# MySens-GWeasySensRS485-V01-014.net
KiCad netlist of a schematic drawn in EAGLE
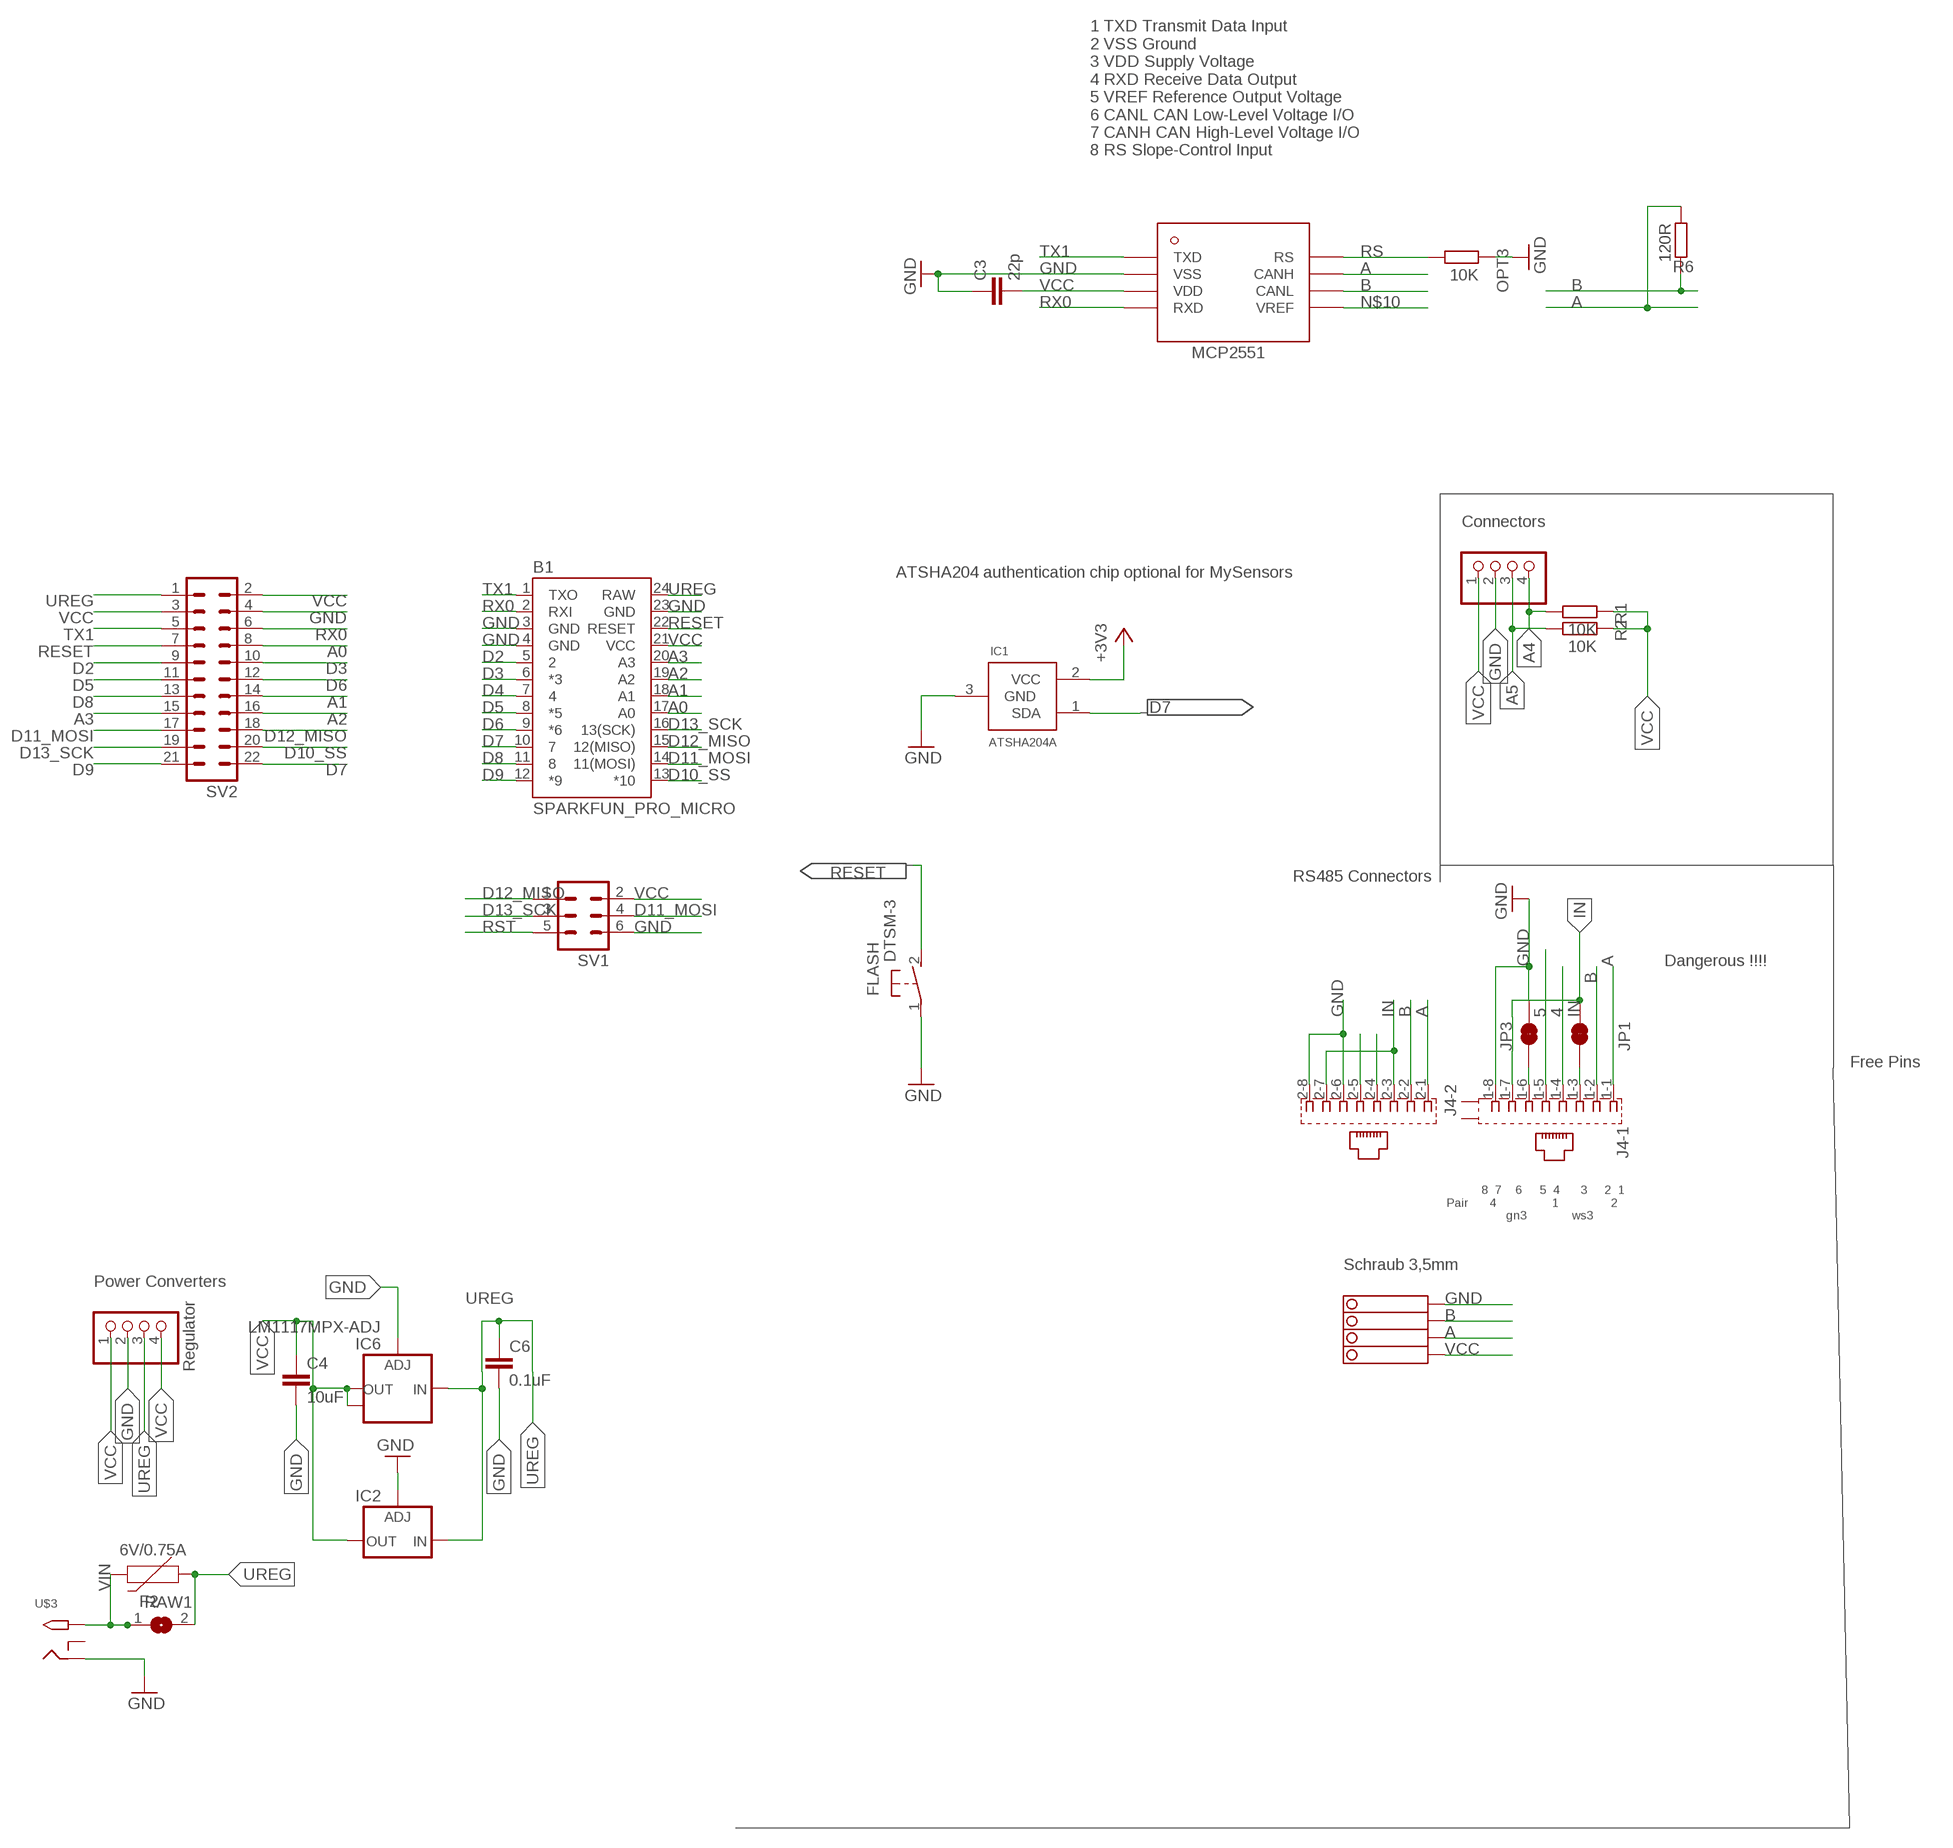
[diagram p0: schematic, sheet 1]

(export (version "E")
  (design (tool "Eeschema 10.0.6"))
  (components
    (comp (ref "B1")
      (value "SPARKFUN_PRO_MICRO")
      (footprint "eagle-import:SPARKFUN_PRO_MICRO")
      (libsource (lib "eagle-import") (part "SPARKFUN_PRO_MICRO"))
    )
    (comp (ref "C3")
      (value "22p")
      (footprint "eagle-import:C0805")
      (libsource (lib "eagle-import") (part "C-EUC0805"))
    )
    (comp (ref "C4")
      (value "10uF")
      (footprint "eagle-import:C1210")
      (libsource (lib "eagle-import") (part "C-EUC1210"))
    )
    (comp (ref "C6")
      (value "0.1uF")
      (footprint "eagle-import:C1206")
      (libsource (lib "eagle-import") (part "C-EUC1206"))
    )
    (comp (ref "F2")
      (value "6V/0.75A")
      (footprint "eagle-import:1206")
      (libsource (lib "eagle-import") (part "PPTC_THREE-QUARTER-AMP"))
    )
    (comp (ref "FLASH")
      (value "DTSM-3")
      (footprint "eagle-import:DTSM-3")
      (libsource (lib "eagle-import") (part "DTSM-3"))
    )
    (comp (ref "IC1")
      (value "ATSHA204A")
      (footprint "eagle-import:SOT23")
      (libsource (lib "eagle-import") (part "ATSHA204A"))
    )
    (comp (ref "IC2")
      (value "LD117ADT50TR")
      (footprint "eagle-import:DPACK")
      (libsource (lib "eagle-import") (part "LD117A?DT50TR"))
    )
    (comp (ref "IC6")
      (value "LM1117MPX-ADJ")
      (footprint "eagle-import:SOT223")
      (libsource (lib "eagle-import") (part "LM1117MPX-ADJ"))
    )
    (comp (ref "J4")
      (value "RJ45_2X_NARROW_SHILDPINS_NOCASE")
      (footprint "eagle-import:RJ45_2X_NARROW_SHILDPINS_NOCASE")
      (libsource (lib "eagle-import") (part "RJ45_2X_NARROW_SHILDPINS_NOCASE"))
    )
    (comp (ref "JP1")
      (value "JUMPER-SMT_2_NC_TRACE_SILK")
      (footprint "eagle-import:SMT-JUMPER_2_NC_TRACE_SILK")
      (libsource (lib "eagle-import") (part "JUMPER-SMT_2_NC_TRACE_SILK"))
    )
    (comp (ref "JP3")
      (value "JUMPER-SMT_2_NC_TRACE_SILK")
      (footprint "eagle-import:SMT-JUMPER_2_NC_TRACE_SILK")
      (libsource (lib "eagle-import") (part "JUMPER-SMT_2_NC_TRACE_SILK"))
    )
    (comp (ref "JP10")
      (value "PINHD-1X04_2.54-S")
      (footprint "eagle-import:1X04-S")
      (libsource (lib "eagle-import") (part "PINHD-1X04_2.54-S"))
    )
    (comp (ref "OPT3")
      (value "10K")
      (footprint "eagle-import:R0805")
      (libsource (lib "eagle-import") (part "R-EU_R0805"))
    )
    (comp (ref "R1")
      (value "10K")
      (footprint "eagle-import:R0805")
      (libsource (lib "eagle-import") (part "R-EU_R0805"))
    )
    (comp (ref "R2")
      (value "10K")
      (footprint "eagle-import:R0805")
      (libsource (lib "eagle-import") (part "R-EU_R0805"))
    )
    (comp (ref "R6")
      (value "120R")
      (footprint "eagle-import:R0805")
      (libsource (lib "eagle-import") (part "R-EU_R0805"))
    )
    (comp (ref "RAW1")
      (value "SJ")
      (footprint "eagle-import:SJ")
      (libsource (lib "eagle-import") (part "SJ"))
    )
    (comp (ref "STEPDWN")
      (value "PINHD-1X04_2.54-S")
      (footprint "eagle-import:1X04-S")
      (libsource (lib "eagle-import") (part "PINHD-1X04_2.54-S"))
    )
    (comp (ref "SV1")
      (value "MA03-2")
      (footprint "eagle-import:MA03-2")
      (libsource (lib "eagle-import") (part "MA03-2"))
    )
    (comp (ref "SV2")
      (value "MA11-2")
      (footprint "eagle-import:MA11-2")
      (libsource (lib "eagle-import") (part "MA11-2"))
    )
    (comp (ref "U$1")
      (value "MCP2551")
      (footprint "eagle-import:SOIC-8")
      (libsource (lib "eagle-import") (part "MCP2551"))
    )
    (comp (ref "U$3")
      (value "2.1MMJACKTHM")
      (footprint "eagle-import:PJ-102A")
      (libsource (lib "eagle-import") (part "2.1MMJACKTHM"))
    )
    (comp (ref "X4")
      (value "1751264")
      (footprint "eagle-import:1751264")
      (libsource (lib "eagle-import") (part "1751264"))
    )
  )
  (nets
    (net (code "1") (name "+3V3") (class "Default")
      (node (ref "IC1") (pin "2") (pinfunction "VCC_2") (pintype "bidirectional"))
    )
    (net (code "2") (name "/4") (class "Default")
      (node (ref "J4") (pin "1-4") (pinfunction "4_1-4") (pintype "passive"))
    )
    (net (code "3") (name "/5") (class "Default")
      (node (ref "J4") (pin "1-5") (pinfunction "5_1-5") (pintype "passive"))
    )
    (net (code "4") (name "/A") (class "Default")
      (node (ref "J4") (pin "1-1") (pinfunction "1_1-1") (pintype "passive"))
      (node (ref "J4") (pin "2-1") (pinfunction "1_2-1") (pintype "passive"))
      (node (ref "R6") (pin "1") (pinfunction "1_1") (pintype "passive"))
      (node (ref "U$1") (pin "CANH") (pinfunction "CANH_CANH") (pintype "bidirectional"))
      (node (ref "X4") (pin "2") (pinfunction "K_2") (pintype "passive"))
    )
    (net (code "5") (name "/A0") (class "Default")
      (node (ref "B1") (pin "17") (pinfunction "A0_17") (pintype "bidirectional"))
      (node (ref "SV2") (pin "8") (pinfunction "8_8") (pintype "passive"))
    )
    (net (code "6") (name "/A1") (class "Default")
      (node (ref "B1") (pin "18") (pinfunction "A1_18") (pintype "bidirectional"))
      (node (ref "SV2") (pin "14") (pinfunction "14_14") (pintype "passive"))
    )
    (net (code "7") (name "/A2") (class "Default")
      (node (ref "B1") (pin "19") (pinfunction "A2_19") (pintype "bidirectional"))
      (node (ref "SV2") (pin "16") (pinfunction "16_16") (pintype "passive"))
    )
    (net (code "8") (name "/A3") (class "Default")
      (node (ref "B1") (pin "20") (pinfunction "A3_20") (pintype "bidirectional"))
      (node (ref "SV2") (pin "15") (pinfunction "15_15") (pintype "passive"))
    )
    (net (code "9") (name "/B") (class "Default")
      (node (ref "J4") (pin "1-2") (pinfunction "2_1-2") (pintype "passive"))
      (node (ref "J4") (pin "2-2") (pinfunction "2_2-2") (pintype "passive"))
      (node (ref "R6") (pin "2") (pinfunction "2_2") (pintype "passive"))
      (node (ref "U$1") (pin "CANL") (pinfunction "CANL_CANL") (pintype "bidirectional"))
      (node (ref "X4") (pin "3") (pinfunction "K_3") (pintype "passive"))
    )
    (net (code "10") (name "/D2") (class "Default")
      (node (ref "B1") (pin "5") (pinfunction "2_5") (pintype "bidirectional"))
      (node (ref "SV2") (pin "9") (pinfunction "9_9") (pintype "passive"))
    )
    (net (code "11") (name "/D3") (class "Default")
      (node (ref "B1") (pin "6") (pinfunction "*3_6") (pintype "bidirectional"))
      (node (ref "SV2") (pin "10") (pinfunction "10_10") (pintype "passive"))
    )
    (net (code "12") (name "/D4") (class "Default")
      (node (ref "B1") (pin "7") (pinfunction "4_7") (pintype "bidirectional"))
    )
    (net (code "13") (name "/D5") (class "Default")
      (node (ref "B1") (pin "8") (pinfunction "*5_8") (pintype "bidirectional"))
      (node (ref "SV2") (pin "11") (pinfunction "11_11") (pintype "passive"))
    )
    (net (code "14") (name "/D6") (class "Default")
      (node (ref "B1") (pin "9") (pinfunction "*6_9") (pintype "bidirectional"))
      (node (ref "SV2") (pin "12") (pinfunction "12_12") (pintype "passive"))
    )
    (net (code "15") (name "/D7") (class "Default")
      (node (ref "B1") (pin "10") (pinfunction "7_10") (pintype "bidirectional"))
      (node (ref "IC1") (pin "1") (pinfunction "SDA_1") (pintype "bidirectional"))
      (node (ref "SV2") (pin "22") (pinfunction "22_22") (pintype "passive"))
    )
    (net (code "16") (name "/D8") (class "Default")
      (node (ref "B1") (pin "11") (pinfunction "8_11") (pintype "bidirectional"))
      (node (ref "SV2") (pin "13") (pinfunction "13_13") (pintype "passive"))
    )
    (net (code "17") (name "/D9") (class "Default")
      (node (ref "B1") (pin "12") (pinfunction "*9_12") (pintype "bidirectional"))
      (node (ref "SV2") (pin "21") (pinfunction "21_21") (pintype "passive"))
    )
    (net (code "18") (name "/D10_SS") (class "Default")
      (node (ref "B1") (pin "13") (pinfunction "*10_13") (pintype "bidirectional"))
      (node (ref "SV2") (pin "20") (pinfunction "20_20") (pintype "passive"))
    )
    (net (code "19") (name "/D11_MOSI") (class "Default")
      (node (ref "B1") (pin "14") (pinfunction "11(MOSI)_14") (pintype "bidirectional"))
      (node (ref "SV1") (pin "4") (pinfunction "4_4") (pintype "passive"))
      (node (ref "SV2") (pin "17") (pinfunction "17_17") (pintype "passive"))
    )
    (net (code "20") (name "/D12_MISO") (class "Default")
      (node (ref "B1") (pin "15") (pinfunction "12(MISO)_15") (pintype "bidirectional"))
      (node (ref "SV1") (pin "1") (pinfunction "1_1") (pintype "passive"))
      (node (ref "SV2") (pin "18") (pinfunction "18_18") (pintype "passive"))
    )
    (net (code "21") (name "/D13_SCK") (class "Default")
      (node (ref "B1") (pin "16") (pinfunction "13(SCK)_16") (pintype "bidirectional"))
      (node (ref "SV1") (pin "3") (pinfunction "3_3") (pintype "passive"))
      (node (ref "SV2") (pin "19") (pinfunction "19_19") (pintype "passive"))
    )
    (net (code "22") (name "/N$10") (class "Default")
      (node (ref "U$1") (pin "VREF") (pinfunction "VREF_VREF") (pintype "bidirectional"))
    )
    (net (code "23") (name "/RESET") (class "Default")
      (node (ref "B1") (pin "22") (pinfunction "RESET_22") (pintype "bidirectional"))
      (node (ref "FLASH") (pin "2") (pinfunction "2_2") (pintype "passive"))
      (node (ref "SV2") (pin "7") (pinfunction "7_7") (pintype "passive"))
    )
    (net (code "24") (name "/RS") (class "Default")
      (node (ref "OPT3") (pin "2") (pinfunction "2_2") (pintype "passive"))
      (node (ref "U$1") (pin "RS") (pinfunction "RS_RS") (pintype "bidirectional"))
    )
    (net (code "25") (name "/RST") (class "Default")
      (node (ref "SV1") (pin "5") (pinfunction "5_5") (pintype "passive"))
    )
    (net (code "26") (name "/RX0") (class "Default")
      (node (ref "B1") (pin "2") (pinfunction "RXI_2") (pintype "bidirectional"))
      (node (ref "SV2") (pin "6") (pinfunction "6_6") (pintype "passive"))
      (node (ref "U$1") (pin "RXD") (pinfunction "RXD_RXD") (pintype "bidirectional"))
    )
    (net (code "27") (name "/TX1") (class "Default")
      (node (ref "B1") (pin "1") (pinfunction "TXO_1") (pintype "bidirectional"))
      (node (ref "SV2") (pin "5") (pinfunction "5_5") (pintype "passive"))
      (node (ref "U$1") (pin "TXD") (pinfunction "TXD_TXD") (pintype "bidirectional"))
    )
    (net (code "28") (name "/VIN") (class "Default")
      (node (ref "F2") (pin "2") (pinfunction "2_2") (pintype "bidirectional"))
      (node (ref "RAW1") (pin "1") (pinfunction "1_1") (pintype "passive"))
      (node (ref "U$3") (pin "TIP") (pinfunction "TIP_TIP") (pintype "bidirectional"))
    )
    (net (code "29") (name "A4") (class "Default")
      (node (ref "JP10") (pin "4") (pinfunction "4_4") (pintype "passive"))
      (node (ref "R1") (pin "2") (pinfunction "2_2") (pintype "passive"))
    )
    (net (code "30") (name "A5") (class "Default")
      (node (ref "JP10") (pin "3") (pinfunction "3_3") (pintype "passive"))
      (node (ref "R2") (pin "2") (pinfunction "2_2") (pintype "passive"))
    )
    (net (code "31") (name "GND") (class "Default")
      (node (ref "B1") (pin "23") (pinfunction "GND_23") (pintype "power_in"))
      (node (ref "B1") (pin "3") (pinfunction "GND_3") (pintype "power_in"))
      (node (ref "B1") (pin "4") (pinfunction "GND_4") (pintype "power_in"))
      (node (ref "C3") (pin "1") (pinfunction "1_1") (pintype "passive"))
      (node (ref "C4") (pin "2") (pinfunction "2_2") (pintype "passive"))
      (node (ref "C6") (pin "2") (pinfunction "2_2") (pintype "passive"))
      (node (ref "FLASH") (pin "1") (pinfunction "1_1") (pintype "passive"))
      (node (ref "IC1") (pin "3") (pinfunction "GND_3") (pintype "bidirectional"))
      (node (ref "IC2") (pin "1") (pinfunction "ADJ_1") (pintype "input"))
      (node (ref "IC6") (pin "1") (pinfunction "ADJ_1") (pintype "input"))
      (node (ref "J4") (pin "1-8") (pinfunction "8_1-8") (pintype "passive"))
      (node (ref "J4") (pin "2-6") (pinfunction "6_2-6") (pintype "passive"))
      (node (ref "J4") (pin "2-8") (pinfunction "8_2-8") (pintype "passive"))
      (node (ref "JP10") (pin "2") (pinfunction "2_2") (pintype "passive"))
      (node (ref "JP3") (pin "2") (pinfunction "2_2") (pintype "passive"))
      (node (ref "OPT3") (pin "1") (pinfunction "1_1") (pintype "passive"))
      (node (ref "STEPDWN") (pin "2") (pinfunction "2_2") (pintype "passive"))
      (node (ref "SV1") (pin "6") (pinfunction "6_6") (pintype "passive"))
      (node (ref "SV2") (pin "4") (pinfunction "4_4") (pintype "passive"))
      (node (ref "U$1") (pin "VSS") (pinfunction "VSS_VSS") (pintype "bidirectional"))
      (node (ref "U$3") (pin "RING") (pinfunction "RING_RING") (pintype "bidirectional"))
      (node (ref "X4") (pin "4") (pinfunction "K_4") (pintype "passive"))
    )
    (net (code "32") (name "IN") (class "Default")
      (node (ref "J4") (pin "1-7") (pinfunction "7_1-7") (pintype "passive"))
      (node (ref "J4") (pin "2-3") (pinfunction "3_2-3") (pintype "passive"))
      (node (ref "J4") (pin "2-7") (pinfunction "7_2-7") (pintype "passive"))
      (node (ref "JP1") (pin "2") (pinfunction "2_2") (pintype "passive"))
    )
    (net (code "33") (name "Net-(J4A-3)") (class "Default")
      (node (ref "J4") (pin "1-3") (pinfunction "3_1-3") (pintype "passive"))
      (node (ref "JP1") (pin "1") (pinfunction "1_1") (pintype "passive"))
    )
    (net (code "34") (name "Net-(J4A-6)") (class "Default")
      (node (ref "J4") (pin "1-6") (pinfunction "6_1-6") (pintype "passive"))
      (node (ref "JP3") (pin "1") (pinfunction "1_1") (pintype "passive"))
    )
    (net (code "35") (name "UREG") (class "Default")
      (node (ref "B1") (pin "24") (pinfunction "RAW_24") (pintype "power_in"))
      (node (ref "C6") (pin "1") (pinfunction "1_1") (pintype "passive"))
      (node (ref "F2") (pin "1") (pinfunction "1_1") (pintype "bidirectional"))
      (node (ref "IC2") (pin "3") (pinfunction "IN_3") (pintype "input"))
      (node (ref "IC6") (pin "3") (pinfunction "IN_3") (pintype "input"))
      (node (ref "RAW1") (pin "2") (pinfunction "2_2") (pintype "passive"))
      (node (ref "STEPDWN") (pin "3") (pinfunction "3_3") (pintype "passive"))
      (node (ref "SV2") (pin "1") (pinfunction "1_1") (pintype "passive"))
    )
    (net (code "36") (name "VCC") (class "Default")
      (node (ref "B1") (pin "21") (pinfunction "VCC_21") (pintype "power_in"))
      (node (ref "C3") (pin "2") (pinfunction "2_2") (pintype "passive"))
      (node (ref "C4") (pin "1") (pinfunction "1_1") (pintype "passive"))
      (node (ref "IC2") (pin "4") (pinfunction "OUT_4") (pintype "passive"))
      (node (ref "IC6") (pin "2") (pinfunction "OUT_2") (pintype "passive"))
      (node (ref "IC6") (pin "TAB") (pinfunction "OUT1_TAB") (pintype "passive"))
      (node (ref "JP10") (pin "1") (pinfunction "1_1") (pintype "passive"))
      (node (ref "R1") (pin "1") (pinfunction "1_1") (pintype "passive"))
      (node (ref "R2") (pin "1") (pinfunction "1_1") (pintype "passive"))
      (node (ref "STEPDWN") (pin "1") (pinfunction "1_1") (pintype "passive"))
      (node (ref "STEPDWN") (pin "4") (pinfunction "4_4") (pintype "passive"))
      (node (ref "SV1") (pin "2") (pinfunction "2_2") (pintype "passive"))
      (node (ref "SV2") (pin "2") (pinfunction "2_2") (pintype "passive"))
      (node (ref "SV2") (pin "3") (pinfunction "3_3") (pintype "passive"))
      (node (ref "U$1") (pin "VDD") (pinfunction "VDD_VDD") (pintype "bidirectional"))
      (node (ref "X4") (pin "1") (pinfunction "K_1") (pintype "passive"))
    )
    (net (code "37") (name "unconnected-(J4A-S1-PadG1)") (class "Default")
      (node (ref "J4") (pin "G1") (pinfunction "S1_G1") (pintype "passive"))
    )
    (net (code "38") (name "unconnected-(J4A-S2-PadG3)") (class "Default")
      (node (ref "J4") (pin "G3") (pinfunction "S2_G3") (pintype "passive"))
    )
    (net (code "39") (name "unconnected-(J4B-4-Pad2-4)") (class "Default")
      (node (ref "J4") (pin "2-4") (pinfunction "4_2-4") (pintype "passive"))
    )
    (net (code "40") (name "unconnected-(J4B-5-Pad2-5)") (class "Default")
      (node (ref "J4") (pin "2-5") (pinfunction "5_2-5") (pintype "passive"))
    )
    (net (code "41") (name "unconnected-(U$3-PadRING_SW)") (class "Default")
      (node (ref "U$3") (pin "RING_SW") (pinfunction "RING_SW_RING_SW") (pintype "bidirectional"))
    )
  )
)
